# Astable-555-Timer.net
KiCad netlist of a schematic drawn in EAGLE
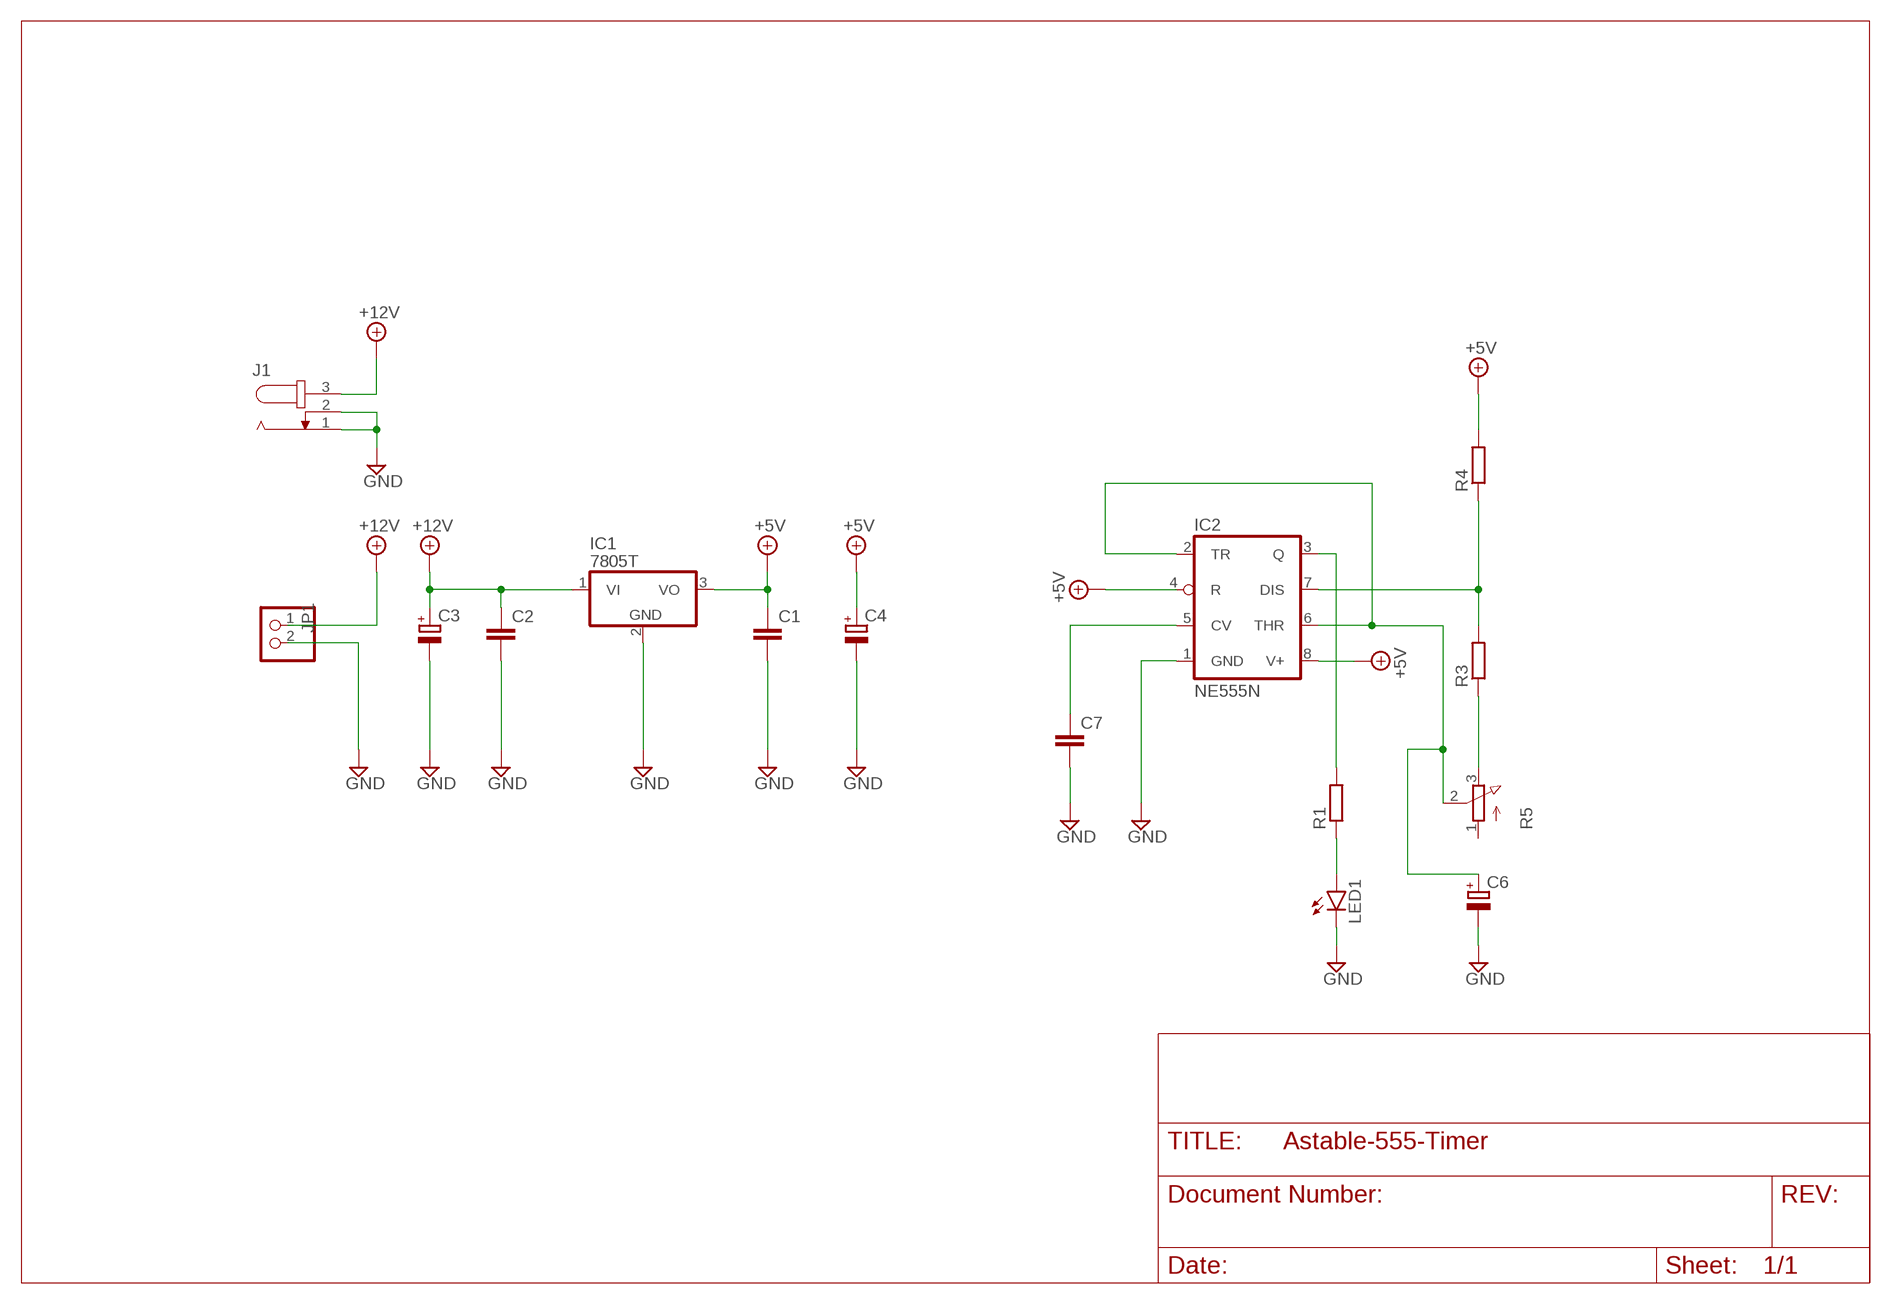
[diagram p0: schematic, sheet 1]

(export (version "E")
  (design (tool "Eeschema 10.0.6"))
  (components
    (comp (ref "C1")
      (value "C-EU050-030X075")
      (footprint "eagle-import:C050-030X075")
      (libsource (lib "eagle-import") (part "C-EU050-030X075"))
    )
    (comp (ref "C2")
      (value "C-EU050-030X075")
      (footprint "eagle-import:C050-030X075")
      (libsource (lib "eagle-import") (part "C-EU050-030X075"))
    )
    (comp (ref "C3")
      (value "CPOL-EUE3.5-8")
      (footprint "eagle-import:E3,5-8")
      (libsource (lib "eagle-import") (part "CPOL-EUE3.5-8"))
    )
    (comp (ref "C4")
      (value "CPOL-EUE3.5-8")
      (footprint "eagle-import:E3,5-8")
      (libsource (lib "eagle-import") (part "CPOL-EUE3.5-8"))
    )
    (comp (ref "C6")
      (value "CPOL-EUE3.5-8")
      (footprint "eagle-import:E3,5-8")
      (libsource (lib "eagle-import") (part "CPOL-EUE3.5-8"))
    )
    (comp (ref "C7")
      (value "C-EU050-030X075")
      (footprint "eagle-import:C050-030X075")
      (libsource (lib "eagle-import") (part "C-EU050-030X075"))
    )
    (comp (ref "IC1")
      (value "7805T")
      (footprint "eagle-import:TO220H")
      (libsource (lib "eagle-import") (part "78T05"))
    )
    (comp (ref "IC2")
      (value "NE555N")
      (footprint "eagle-import:DIL08")
      (libsource (lib "eagle-import") (part "555NNE"))
    )
    (comp (ref "J1")
      (value "JACK-PLUG1")
      (footprint "eagle-import:SPC4078")
      (libsource (lib "eagle-import") (part "JACK-PLUG1"))
    )
    (comp (ref "JP1")
      (value "PINHD-1X2")
      (footprint "eagle-import:1X02")
      (libsource (lib "eagle-import") (part "PINHD-1X2"))
    )
    (comp (ref "LED1")
      (value "LED5MM")
      (footprint "eagle-import:LED5MM")
      (libsource (lib "eagle-import") (part "LED5MM"))
    )
    (comp (ref "R1")
      (value "R-EU_0207/10")
      (footprint "eagle-import:0207_10")
      (libsource (lib "eagle-import") (part "R-EU_0207/10"))
    )
    (comp (ref "R3")
      (value "R-EU_0207/10")
      (footprint "eagle-import:0207_10")
      (libsource (lib "eagle-import") (part "R-EU_0207/10"))
    )
    (comp (ref "R4")
      (value "R-EU_0207/10")
      (footprint "eagle-import:0207_10")
      (libsource (lib "eagle-import") (part "R-EU_0207/10"))
    )
    (comp (ref "R5")
      (value "3RP/1610N")
      (footprint "eagle-import:3RP_1610N")
      (libsource (lib "eagle-import") (part "3RP/1610N"))
    )
  )
  (nets
    (net (code "1") (name "+5V") (class "Default")
      (node (ref "C1") (pin "1") (pinfunction "1_1") (pintype "passive"))
      (node (ref "C4") (pin "+") (pinfunction "+_+") (pintype "passive"))
      (node (ref "IC1") (pin "3") (pinfunction "VO_3") (pintype "passive"))
      (node (ref "IC2") (pin "4") (pinfunction "R_4") (pintype "input"))
      (node (ref "IC2") (pin "8") (pinfunction "V+_8") (pintype "power_in"))
      (node (ref "R4") (pin "2") (pinfunction "2_2") (pintype "passive"))
    )
    (net (code "2") (name "+12V") (class "Default")
      (node (ref "C2") (pin "1") (pinfunction "1_1") (pintype "passive"))
      (node (ref "C3") (pin "+") (pinfunction "+_+") (pintype "passive"))
      (node (ref "IC1") (pin "1") (pinfunction "VI_1") (pintype "input"))
      (node (ref "J1") (pin "3") (pinfunction "3_3") (pintype "passive"))
      (node (ref "JP1") (pin "1") (pinfunction "1_1") (pintype "passive"))
    )
    (net (code "3") (name "GND") (class "Default")
      (node (ref "C1") (pin "2") (pinfunction "2_2") (pintype "passive"))
      (node (ref "C2") (pin "2") (pinfunction "2_2") (pintype "passive"))
      (node (ref "C3") (pin "-") (pinfunction "-_-") (pintype "passive"))
      (node (ref "C4") (pin "-") (pinfunction "-_-") (pintype "passive"))
      (node (ref "C6") (pin "-") (pinfunction "-_-") (pintype "passive"))
      (node (ref "C7") (pin "2") (pinfunction "2_2") (pintype "passive"))
      (node (ref "IC1") (pin "2") (pinfunction "GND_2") (pintype "passive"))
      (node (ref "IC2") (pin "1") (pinfunction "GND_1") (pintype "power_in"))
      (node (ref "J1") (pin "1") (pinfunction "1_1") (pintype "passive"))
      (node (ref "J1") (pin "2") (pinfunction "2_2") (pintype "passive"))
      (node (ref "JP1") (pin "2") (pinfunction "2_2") (pintype "passive"))
      (node (ref "LED1") (pin "K") (pinfunction "C_K") (pintype "passive"))
    )
    (net (code "4") (name "Net-(IC2-CV)") (class "Default")
      (node (ref "C7") (pin "1") (pinfunction "1_1") (pintype "passive"))
      (node (ref "IC2") (pin "5") (pinfunction "CV_5") (pintype "input"))
    )
    (net (code "5") (name "Net-(IC2-DIS)") (class "Default")
      (node (ref "IC2") (pin "7") (pinfunction "DIS_7") (pintype "input"))
      (node (ref "R3") (pin "2") (pinfunction "2_2") (pintype "passive"))
      (node (ref "R4") (pin "1") (pinfunction "1_1") (pintype "passive"))
    )
    (net (code "6") (name "Net-(IC2-Q)") (class "Default")
      (node (ref "IC2") (pin "3") (pinfunction "Q_3") (pintype "output"))
      (node (ref "R1") (pin "2") (pinfunction "2_2") (pintype "passive"))
    )
    (net (code "7") (name "Net-(IC2-THR)") (class "Default")
      (node (ref "C6") (pin "+") (pinfunction "+_+") (pintype "passive"))
      (node (ref "IC2") (pin "2") (pinfunction "TR_2") (pintype "input"))
      (node (ref "IC2") (pin "6") (pinfunction "THR_6") (pintype "input"))
      (node (ref "R5") (pin "2") (pinfunction "S_2") (pintype "passive"))
    )
    (net (code "8") (name "Net-(LED1-PadA)") (class "Default")
      (node (ref "LED1") (pin "A") (pinfunction "A_A") (pintype "passive"))
      (node (ref "R1") (pin "1") (pinfunction "1_1") (pintype "passive"))
    )
    (net (code "9") (name "Net-(R5-E)") (class "Default")
      (node (ref "R3") (pin "1") (pinfunction "1_1") (pintype "passive"))
      (node (ref "R5") (pin "3") (pinfunction "E_3") (pintype "passive"))
    )
    (net (code "10") (name "unconnected-(R5-A-Pad1)") (class "Default")
      (node (ref "R5") (pin "1") (pinfunction "A_1") (pintype "passive"))
    )
  )
)
